# 5_ButtonsAndLeds.net
KiCad netlist of a schematic drawn in Altium Designer
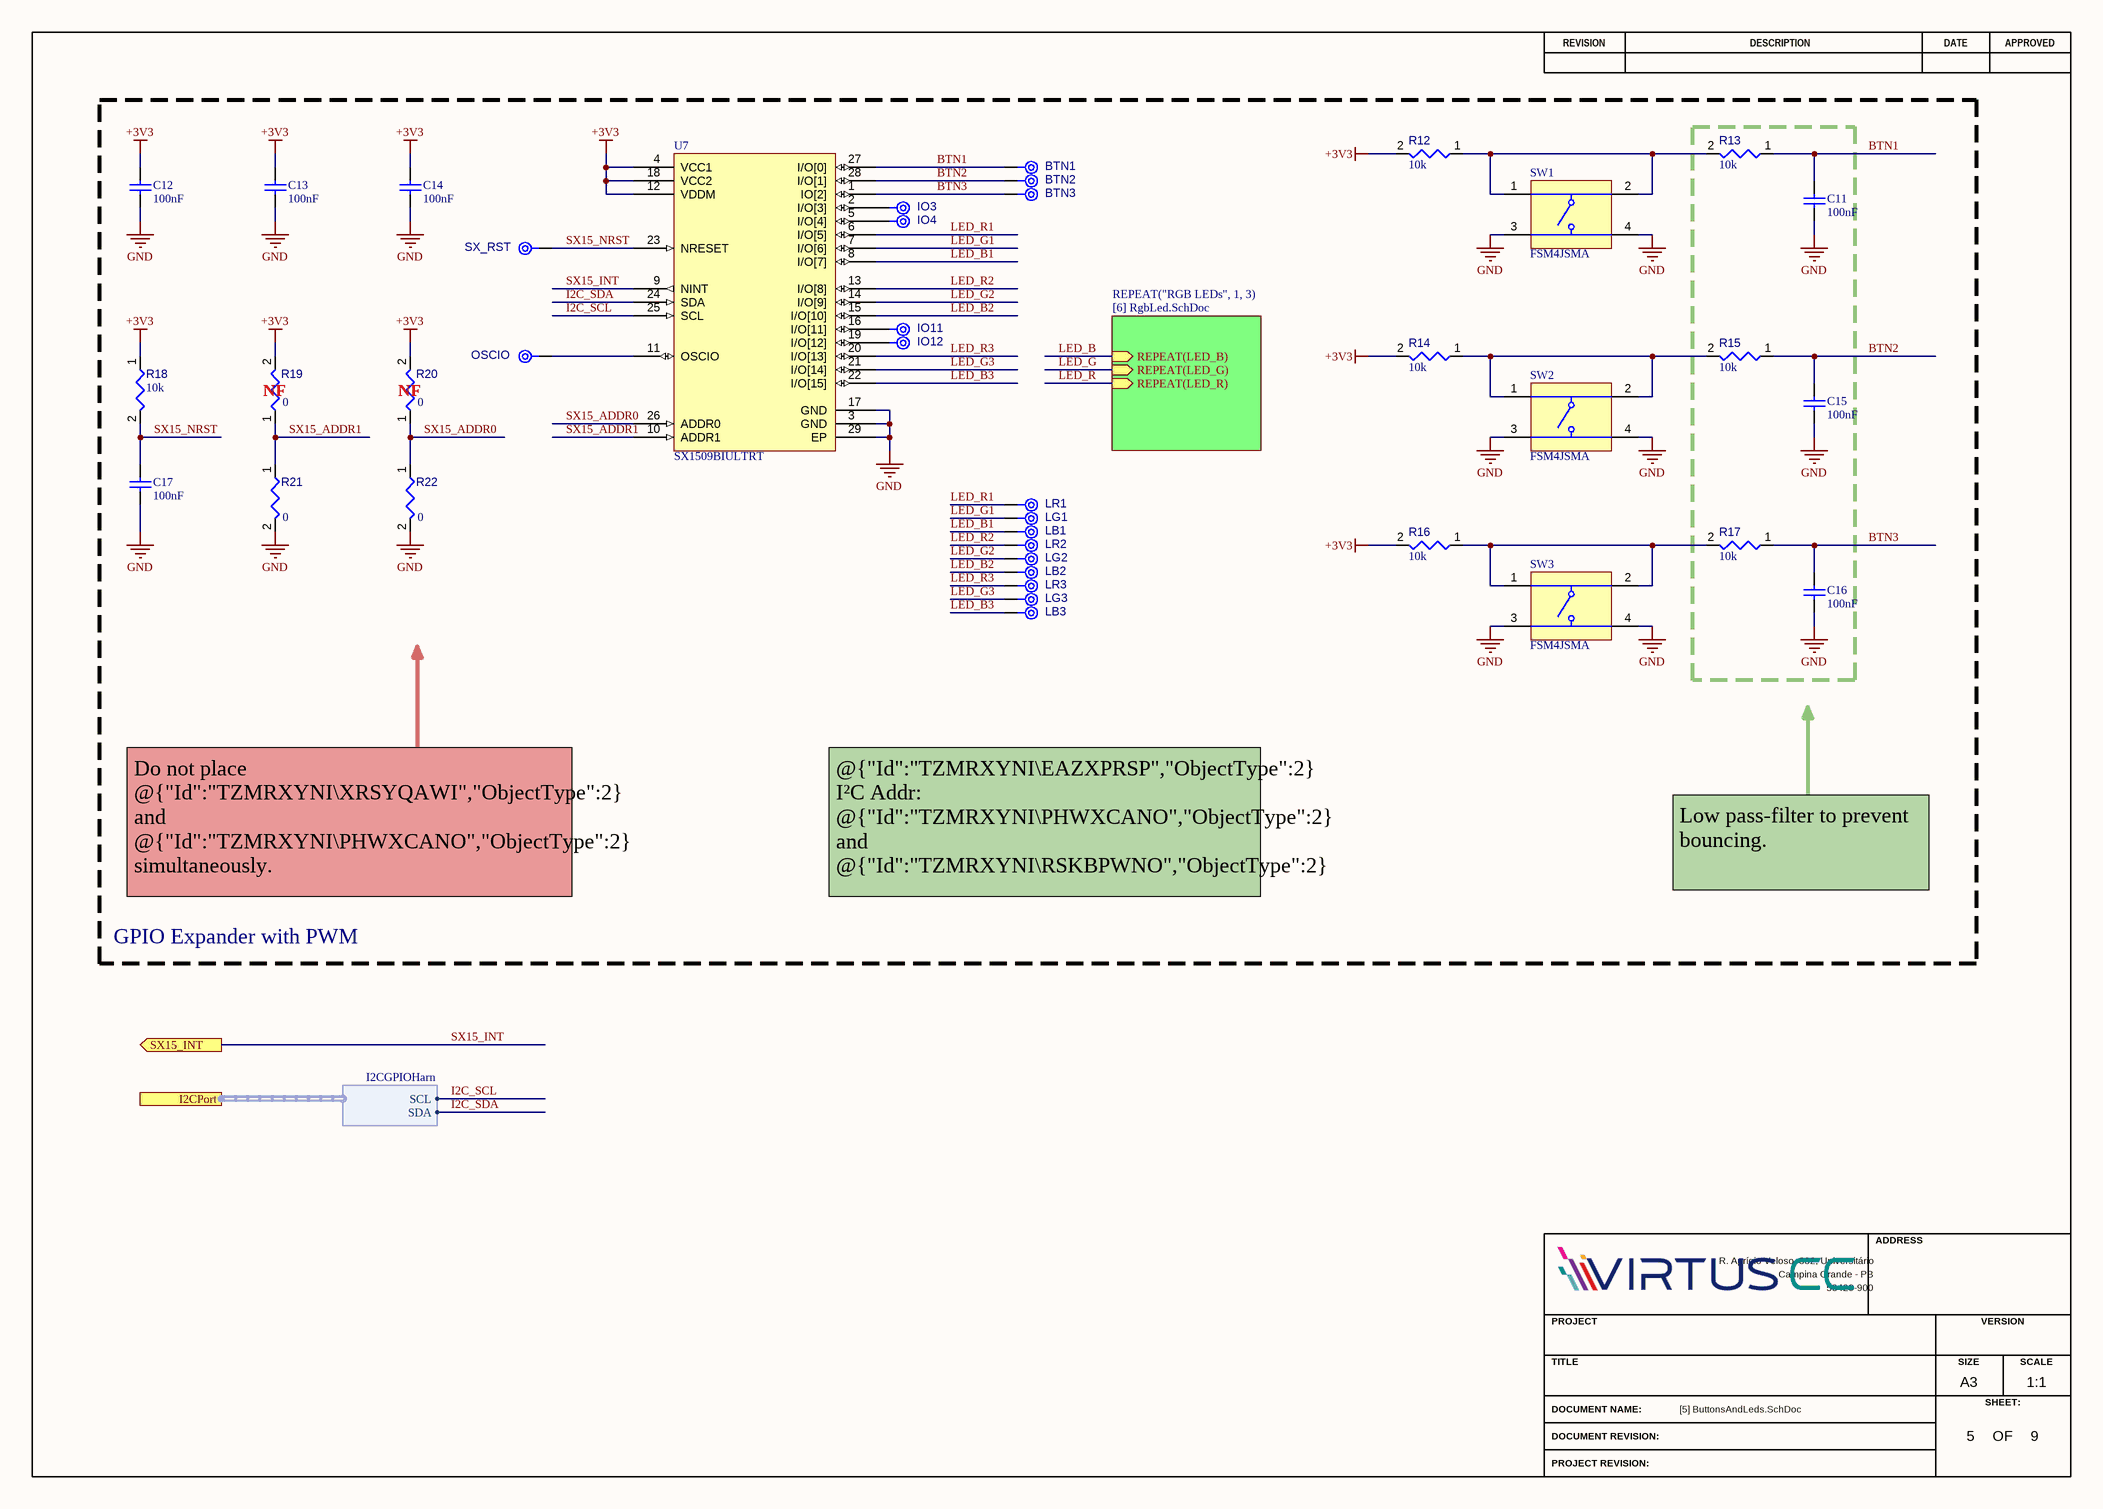
[diagram p0: [5] ButtonsAndLeds.SchDoc]

(export (version "E")
  (design (tool "Eeschema 10.0.6"))
  (components
    (comp (ref "BTN1")
      (value "TPAD6R")
      (footprint "TP06R")
      (description "0.6mm round")
      (libsource (lib "UFCG - Universidade Federal de Campina Grande") (part "CMP-001-0001-4"))
    )
    (comp (ref "BTN2")
      (value "TPAD6R")
      (footprint "TP06R")
      (description "0.6mm round")
      (libsource (lib "UFCG - Universidade Federal de Campina Grande") (part "CMP-001-0001-4"))
    )
    (comp (ref "BTN3")
      (value "TPAD6R")
      (footprint "TP06R")
      (description "0.6mm round")
      (libsource (lib "UFCG - Universidade Federal de Campina Grande") (part "CMP-001-0001-4"))
    )
    (comp (ref "C11")
      (value "100nF")
      (footprint "CAPC0603(1608)100_L")
      (description "Multilayer Ceramic Capacitor, 0.1 uF, 16 V, ± 20%, X7R, 0603 [1608 Metric]")
      (fields (field (name "TOLERANCE") "20%") (field (name "Comment") "VJ0603Y104MXJCW1BC"))
      (libsource (lib "UFCG - Universidade Federal de Campina Grande") (part "CAP"))
    )
    (comp (ref "C12")
      (value "100nF")
      (footprint "CAPC0603(1608)100_L")
      (description "Multilayer Ceramic Capacitor, 0.1 uF, 16 V, ± 20%, X7R, 0603 [1608 Metric]")
      (fields (field (name "TOLERANCE") "20%") (field (name "Comment") "VJ0603Y104MXJCW1BC"))
      (libsource (lib "UFCG - Universidade Federal de Campina Grande") (part "CAP"))
    )
    (comp (ref "C13")
      (value "100nF")
      (footprint "CAPC0603(1608)100_L")
      (description "Multilayer Ceramic Capacitor, 0.1 uF, 16 V, ± 20%, X7R, 0603 [1608 Metric]")
      (fields (field (name "TOLERANCE") "20%") (field (name "Comment") "VJ0603Y104MXJCW1BC"))
      (libsource (lib "UFCG - Universidade Federal de Campina Grande") (part "CAP"))
    )
    (comp (ref "C14")
      (value "100nF")
      (footprint "CAPC0603(1608)100_L")
      (description "Multilayer Ceramic Capacitor, 0.1 uF, 16 V, ± 20%, X7R, 0603 [1608 Metric]")
      (fields (field (name "TOLERANCE") "20%") (field (name "Comment") "VJ0603Y104MXJCW1BC"))
      (libsource (lib "UFCG - Universidade Federal de Campina Grande") (part "CAP"))
    )
    (comp (ref "C15")
      (value "100nF")
      (footprint "CAPC0603(1608)100_L")
      (description "Multilayer Ceramic Capacitor, 0.1 uF, 16 V, ± 20%, X7R, 0603 [1608 Metric]")
      (fields (field (name "TOLERANCE") "20%") (field (name "Comment") "VJ0603Y104MXJCW1BC"))
      (libsource (lib "UFCG - Universidade Federal de Campina Grande") (part "CAP"))
    )
    (comp (ref "C16")
      (value "100nF")
      (footprint "CAPC0603(1608)100_L")
      (description "Multilayer Ceramic Capacitor, 0.1 uF, 16 V, ± 20%, X7R, 0603 [1608 Metric]")
      (fields (field (name "TOLERANCE") "20%") (field (name "Comment") "VJ0603Y104MXJCW1BC"))
      (libsource (lib "UFCG - Universidade Federal de Campina Grande") (part "CAP"))
    )
    (comp (ref "C17")
      (value "100nF")
      (footprint "CAPC0603(1608)100_L")
      (description "Multilayer Ceramic Capacitor, 0.1 uF, 16 V, ± 20%, X7R, 0603 [1608 Metric]")
      (fields (field (name "TOLERANCE") "20%") (field (name "Comment") "VJ0603Y104MXJCW1BC"))
      (libsource (lib "UFCG - Universidade Federal de Campina Grande") (part "CAP"))
    )
    (comp (ref "IO3")
      (value "TPAD6R")
      (footprint "TP06R")
      (description "0.6mm round")
      (libsource (lib "UFCG - Universidade Federal de Campina Grande") (part "CMP-001-0001-4"))
    )
    (comp (ref "IO4")
      (value "TPAD6R")
      (footprint "TP06R")
      (description "0.6mm round")
      (libsource (lib "UFCG - Universidade Federal de Campina Grande") (part "CMP-001-0001-4"))
    )
    (comp (ref "IO11")
      (value "TPAD6R")
      (footprint "TP06R")
      (description "0.6mm round")
      (libsource (lib "UFCG - Universidade Federal de Campina Grande") (part "CMP-001-0001-4"))
    )
    (comp (ref "IO12")
      (value "TPAD6R")
      (footprint "TP06R")
      (description "0.6mm round")
      (libsource (lib "UFCG - Universidade Federal de Campina Grande") (part "CMP-001-0001-4"))
    )
    (comp (ref "LB1")
      (value "TPAD6R")
      (footprint "TP06R")
      (description "0.6mm round")
      (libsource (lib "UFCG - Universidade Federal de Campina Grande") (part "CMP-001-0001-4"))
    )
    (comp (ref "LB2")
      (value "TPAD6R")
      (footprint "TP06R")
      (description "0.6mm round")
      (libsource (lib "UFCG - Universidade Federal de Campina Grande") (part "CMP-001-0001-4"))
    )
    (comp (ref "LB3")
      (value "TPAD6R")
      (footprint "TP06R")
      (description "0.6mm round")
      (libsource (lib "UFCG - Universidade Federal de Campina Grande") (part "CMP-001-0001-4"))
    )
    (comp (ref "LG1")
      (value "TPAD6R")
      (footprint "TP06R")
      (description "0.6mm round")
      (libsource (lib "UFCG - Universidade Federal de Campina Grande") (part "CMP-001-0001-4"))
    )
    (comp (ref "LG2")
      (value "TPAD6R")
      (footprint "TP06R")
      (description "0.6mm round")
      (libsource (lib "UFCG - Universidade Federal de Campina Grande") (part "CMP-001-0001-4"))
    )
    (comp (ref "LG3")
      (value "TPAD6R")
      (footprint "TP06R")
      (description "0.6mm round")
      (libsource (lib "UFCG - Universidade Federal de Campina Grande") (part "CMP-001-0001-4"))
    )
    (comp (ref "LR1")
      (value "TPAD6R")
      (footprint "TP06R")
      (description "0.6mm round")
      (libsource (lib "UFCG - Universidade Federal de Campina Grande") (part "CMP-001-0001-4"))
    )
    (comp (ref "LR2")
      (value "TPAD6R")
      (footprint "TP06R")
      (description "0.6mm round")
      (libsource (lib "UFCG - Universidade Federal de Campina Grande") (part "CMP-001-0001-4"))
    )
    (comp (ref "LR3")
      (value "TPAD6R")
      (footprint "TP06R")
      (description "0.6mm round")
      (libsource (lib "UFCG - Universidade Federal de Campina Grande") (part "CMP-001-0001-4"))
    )
    (comp (ref "OSCIO")
      (value "TPAD6R")
      (footprint "TP06R")
      (description "0.6mm round")
      (libsource (lib "UFCG - Universidade Federal de Campina Grande") (part "CMP-001-0001-4"))
    )
    (comp (ref "R12")
      (value "10k")
      (footprint "RESC0603(1608)_L")
      (description "Chip Resistor, 10 KOhm, +/- 1%, 01 W, -55 to 155 degC, 0603 (1608 Metric)")
      (fields (field (name "POWER") "100mW") (field (name "TOLERANCE") "1%"))
      (libsource (lib "UFCG - Universidade Federal de Campina Grande") (part "RES-2"))
    )
    (comp (ref "R13")
      (value "10k")
      (footprint "RESC0603(1608)_L")
      (description "Chip Resistor, 10 KOhm, +/- 1%, 01 W, -55 to 155 degC, 0603 (1608 Metric)")
      (fields (field (name "POWER") "100mW") (field (name "TOLERANCE") "1%"))
      (libsource (lib "UFCG - Universidade Federal de Campina Grande") (part "RES-2"))
    )
    (comp (ref "R14")
      (value "10k")
      (footprint "RESC0603(1608)_L")
      (description "Chip Resistor, 10 KOhm, +/- 1%, 01 W, -55 to 155 degC, 0603 (1608 Metric)")
      (fields (field (name "POWER") "100mW") (field (name "TOLERANCE") "1%"))
      (libsource (lib "UFCG - Universidade Federal de Campina Grande") (part "RES-2"))
    )
    (comp (ref "R15")
      (value "10k")
      (footprint "RESC0603(1608)_L")
      (description "Chip Resistor, 10 KOhm, +/- 1%, 01 W, -55 to 155 degC, 0603 (1608 Metric)")
      (fields (field (name "POWER") "100mW") (field (name "TOLERANCE") "1%"))
      (libsource (lib "UFCG - Universidade Federal de Campina Grande") (part "RES-2"))
    )
    (comp (ref "R16")
      (value "10k")
      (footprint "RESC0603(1608)_L")
      (description "Chip Resistor, 10 KOhm, +/- 1%, 01 W, -55 to 155 degC, 0603 (1608 Metric)")
      (fields (field (name "POWER") "100mW") (field (name "TOLERANCE") "1%"))
      (libsource (lib "UFCG - Universidade Federal de Campina Grande") (part "RES-2"))
    )
    (comp (ref "R17")
      (value "10k")
      (footprint "RESC0603(1608)_L")
      (description "Chip Resistor, 10 KOhm, +/- 1%, 01 W, -55 to 155 degC, 0603 (1608 Metric)")
      (fields (field (name "POWER") "100mW") (field (name "TOLERANCE") "1%"))
      (libsource (lib "UFCG - Universidade Federal de Campina Grande") (part "RES-2"))
    )
    (comp (ref "R18")
      (value "10k")
      (footprint "RESC0603(1608)_L")
      (description "Chip Resistor, 10 KOhm, +/- 1%, 01 W, -55 to 155 degC, 0603 (1608 Metric)")
      (fields (field (name "POWER") "100mW") (field (name "TOLERANCE") "1%"))
      (libsource (lib "UFCG - Universidade Federal de Campina Grande") (part "RES-2"))
    )
    (comp (ref "R19")
      (value "0")
      (footprint "RESC0603(1608)_L")
      (description "Chip Resistor, 0 Ohm, 0.1 W, -55 to 155 degC, 0603 (1608 Metric)")
      (fields (field (name "TOLERANCE") "5%") (field (name "POWER") "100mW"))
      (libsource (lib "UFCG - Universidade Federal de Campina Grande") (part "RES-2"))
    )
    (comp (ref "R20")
      (value "0")
      (footprint "RESC0603(1608)_L")
      (description "Chip Resistor, 0 Ohm, 0.1 W, -55 to 155 degC, 0603 (1608 Metric)")
      (fields (field (name "TOLERANCE") "5%") (field (name "POWER") "100mW"))
      (libsource (lib "UFCG - Universidade Federal de Campina Grande") (part "RES-2"))
    )
    (comp (ref "R21")
      (value "0")
      (footprint "RESC0603(1608)_L")
      (description "Chip Resistor, 0 Ohm, 0.1 W, -55 to 155 degC, 0603 (1608 Metric)")
      (fields (field (name "TOLERANCE") "5%") (field (name "POWER") "100mW"))
      (libsource (lib "UFCG - Universidade Federal de Campina Grande") (part "RES-2"))
    )
    (comp (ref "R22")
      (value "0")
      (footprint "RESC0603(1608)_L")
      (description "Chip Resistor, 0 Ohm, 0.1 W, -55 to 155 degC, 0603 (1608 Metric)")
      (fields (field (name "TOLERANCE") "5%") (field (name "POWER") "100mW"))
      (libsource (lib "UFCG - Universidade Federal de Campina Grande") (part "RES-2"))
    )
    (comp (ref "SW1")
      (value "FSM4JSMA")
      (footprint "TECO-FSM4JSMA_V")
      (description "Switch Tactile OFF (ON) SPST Round Button Gull Wing 0.05A 12VDC 1.57N SMD Loose Piece")
      (libsource (lib "UFCG - Universidade Federal de Campina Grande") (part "SW-SPST-4_A"))
    )
    (comp (ref "SW2")
      (value "FSM4JSMA")
      (footprint "TECO-FSM4JSMA_V")
      (description "Switch Tactile OFF (ON) SPST Round Button Gull Wing 0.05A 12VDC 1.57N SMD Loose Piece")
      (libsource (lib "UFCG - Universidade Federal de Campina Grande") (part "SW-SPST-4_A"))
    )
    (comp (ref "SW3")
      (value "FSM4JSMA")
      (footprint "TECO-FSM4JSMA_V")
      (description "Switch Tactile OFF (ON) SPST Round Button Gull Wing 0.05A 12VDC 1.57N SMD Loose Piece")
      (libsource (lib "UFCG - Universidade Federal de Campina Grande") (part "SW-SPST-4_A"))
    )
    (comp (ref "SX_RST")
      (value "TPAD6R")
      (footprint "TP06R")
      (description "0.6mm round")
      (libsource (lib "UFCG - Universidade Federal de Campina Grande") (part "CMP-001-0001-4"))
    )
    (comp (ref "U7")
      (value "SX1509BIULTRT")
      (footprint "QFN40P410X410X60_HS-29N")
      (description "IC Gpio Expander I2C 16CH 28QFN / I2C Interface 5.5V 28-PIN Qfn-ut Ep T/r")
      (libsource (lib "UFCG - Universidade Federal de Campina Grande") (part "New symbol 1"))
    )
  )
  (nets
    (net (code "2") (name "+3V3") (class "Default")
      (node (ref "C12") (pin "2") (pinfunction "2_2") (pintype "passive"))
      (node (ref "C13") (pin "2") (pinfunction "2_2") (pintype "passive"))
      (node (ref "C14") (pin "2") (pinfunction "2_2") (pintype "passive"))
      (node (ref "R12") (pin "2") (pinfunction "2_2") (pintype "passive"))
      (node (ref "R14") (pin "2") (pinfunction "2_2") (pintype "passive"))
      (node (ref "R16") (pin "2") (pinfunction "2_2") (pintype "passive"))
      (node (ref "R18") (pin "1") (pinfunction "1_1") (pintype "passive"))
      (node (ref "R19") (pin "2") (pinfunction "2_2") (pintype "passive"))
      (node (ref "R20") (pin "2") (pinfunction "2_2") (pintype "passive"))
      (node (ref "U7") (pin "12") (pinfunction "VDDM_12") (pintype "power_in"))
      (node (ref "U7") (pin "18") (pinfunction "VCC2_18") (pintype "power_in"))
      (node (ref "U7") (pin "4") (pinfunction "VCC1_4") (pintype "power_in"))
    )
    (net (code "3") (name "/BTN1") (class "Default")
      (node (ref "BTN1") (pin "1") (pinfunction "TP_1") (pintype "passive"))
      (node (ref "C11") (pin "2") (pinfunction "2_2") (pintype "passive"))
      (node (ref "R13") (pin "1") (pinfunction "1_1") (pintype "passive"))
      (node (ref "U7") (pin "27") (pinfunction "I/O[0]_27") (pintype "bidirectional"))
    )
    (net (code "4") (name "/BTN2") (class "Default")
      (node (ref "BTN2") (pin "1") (pinfunction "TP_1") (pintype "passive"))
      (node (ref "C15") (pin "2") (pinfunction "2_2") (pintype "passive"))
      (node (ref "R15") (pin "1") (pinfunction "1_1") (pintype "passive"))
      (node (ref "U7") (pin "28") (pinfunction "I/O[1]_28") (pintype "bidirectional"))
    )
    (net (code "5") (name "/BTN3") (class "Default")
      (node (ref "BTN3") (pin "1") (pinfunction "TP_1") (pintype "passive"))
      (node (ref "C16") (pin "2") (pinfunction "2_2") (pintype "passive"))
      (node (ref "R17") (pin "1") (pinfunction "1_1") (pintype "passive"))
      (node (ref "U7") (pin "1") (pinfunction "IO[2]_1") (pintype "bidirectional"))
    )
    (net (code "6") (name "/I2C_SCL") (class "Default")
      (node (ref "U7") (pin "25") (pinfunction "SCL_25") (pintype "input"))
    )
    (net (code "7") (name "/I2C_SDA") (class "Default")
      (node (ref "U7") (pin "24") (pinfunction "SDA_24") (pintype "input"))
    )
    (net (code "9") (name "/LED_B1") (class "Default")
      (node (ref "LB1") (pin "1") (pinfunction "TP_1") (pintype "passive"))
      (node (ref "U7") (pin "8") (pinfunction "I/O[7]_8") (pintype "bidirectional"))
    )
    (net (code "10") (name "/LED_B2") (class "Default")
      (node (ref "LB2") (pin "1") (pinfunction "TP_1") (pintype "passive"))
      (node (ref "U7") (pin "15") (pinfunction "I/O[10]_15") (pintype "bidirectional"))
    )
    (net (code "11") (name "/LED_B3") (class "Default")
      (node (ref "LB3") (pin "1") (pinfunction "TP_1") (pintype "passive"))
      (node (ref "U7") (pin "22") (pinfunction "I/O[15]_22") (pintype "bidirectional"))
    )
    (net (code "13") (name "/LED_G1") (class "Default")
      (node (ref "LG1") (pin "1") (pinfunction "TP_1") (pintype "passive"))
      (node (ref "U7") (pin "7") (pinfunction "I/O[6]_7") (pintype "bidirectional"))
    )
    (net (code "14") (name "/LED_G2") (class "Default")
      (node (ref "LG2") (pin "1") (pinfunction "TP_1") (pintype "passive"))
      (node (ref "U7") (pin "14") (pinfunction "I/O[9]_14") (pintype "bidirectional"))
    )
    (net (code "15") (name "/LED_G3") (class "Default")
      (node (ref "LG3") (pin "1") (pinfunction "TP_1") (pintype "passive"))
      (node (ref "U7") (pin "21") (pinfunction "I/O[14]_21") (pintype "bidirectional"))
    )
    (net (code "17") (name "/LED_R1") (class "Default")
      (node (ref "LR1") (pin "1") (pinfunction "TP_1") (pintype "passive"))
      (node (ref "U7") (pin "6") (pinfunction "I/O[5]_6") (pintype "bidirectional"))
    )
    (net (code "18") (name "/LED_R2") (class "Default")
      (node (ref "LR2") (pin "1") (pinfunction "TP_1") (pintype "passive"))
      (node (ref "U7") (pin "13") (pinfunction "I/O[8]_13") (pintype "bidirectional"))
    )
    (net (code "19") (name "/LED_R3") (class "Default")
      (node (ref "LR3") (pin "1") (pinfunction "TP_1") (pintype "passive"))
      (node (ref "U7") (pin "20") (pinfunction "I/O[13]_20") (pintype "bidirectional"))
    )
    (net (code "20") (name "/SX15_ADDR0") (class "Default")
      (node (ref "R20") (pin "1") (pinfunction "1_1") (pintype "passive"))
      (node (ref "R22") (pin "1") (pinfunction "1_1") (pintype "passive"))
      (node (ref "U7") (pin "26") (pinfunction "ADDR0_26") (pintype "input"))
    )
    (net (code "21") (name "/SX15_ADDR1") (class "Default")
      (node (ref "R19") (pin "1") (pinfunction "1_1") (pintype "passive"))
      (node (ref "R21") (pin "1") (pinfunction "1_1") (pintype "passive"))
      (node (ref "U7") (pin "10") (pinfunction "ADDR1_10") (pintype "input"))
    )
    (net (code "22") (name "/SX15_INT") (class "Default")
      (node (ref "U7") (pin "9") (pinfunction "NINT_9") (pintype "output"))
    )
    (net (code "23") (name "/SX15_NRST") (class "Default")
      (node (ref "C17") (pin "2") (pinfunction "2_2") (pintype "passive"))
      (node (ref "R18") (pin "2") (pinfunction "2_2") (pintype "passive"))
      (node (ref "SX_RST") (pin "1") (pinfunction "TP_1") (pintype "passive"))
      (node (ref "U7") (pin "23") (pinfunction "NRESET_23") (pintype "input"))
    )
    (net (code "25") (name "GND") (class "Default")
      (node (ref "C11") (pin "1") (pinfunction "1_1") (pintype "passive"))
      (node (ref "C12") (pin "1") (pinfunction "1_1") (pintype "passive"))
      (node (ref "C13") (pin "1") (pinfunction "1_1") (pintype "passive"))
      (node (ref "C14") (pin "1") (pinfunction "1_1") (pintype "passive"))
      (node (ref "C15") (pin "1") (pinfunction "1_1") (pintype "passive"))
      (node (ref "C16") (pin "1") (pinfunction "1_1") (pintype "passive"))
      (node (ref "C17") (pin "1") (pinfunction "1_1") (pintype "passive"))
      (node (ref "R21") (pin "2") (pinfunction "2_2") (pintype "passive"))
      (node (ref "R22") (pin "2") (pinfunction "2_2") (pintype "passive"))
      (node (ref "SW1") (pin "3") (pinfunction "3_3") (pintype "passive"))
      (node (ref "SW1") (pin "4") (pinfunction "4_4") (pintype "passive"))
      (node (ref "SW2") (pin "3") (pinfunction "3_3") (pintype "passive"))
      (node (ref "SW2") (pin "4") (pinfunction "4_4") (pintype "passive"))
      (node (ref "SW3") (pin "3") (pinfunction "3_3") (pintype "passive"))
      (node (ref "SW3") (pin "4") (pinfunction "4_4") (pintype "passive"))
      (node (ref "U7") (pin "17") (pinfunction "GND_17") (pintype "power_in"))
      (node (ref "U7") (pin "29") (pinfunction "EP_29") (pintype "power_in"))
      (node (ref "U7") (pin "3") (pinfunction "GND_3") (pintype "power_in"))
    )
    (net (code "26") (name "Net-(IO3-TP)") (class "Default")
      (node (ref "IO3") (pin "1") (pinfunction "TP_1") (pintype "passive"))
      (node (ref "U7") (pin "2") (pinfunction "I/O[3]_2") (pintype "bidirectional"))
    )
    (net (code "27") (name "Net-(IO4-TP)") (class "Default")
      (node (ref "IO4") (pin "1") (pinfunction "TP_1") (pintype "passive"))
      (node (ref "U7") (pin "5") (pinfunction "I/O[4]_5") (pintype "bidirectional"))
    )
    (net (code "28") (name "Net-(IO11-TP)") (class "Default")
      (node (ref "IO11") (pin "1") (pinfunction "TP_1") (pintype "passive"))
      (node (ref "U7") (pin "16") (pinfunction "I/O[11]_16") (pintype "bidirectional"))
    )
    (net (code "29") (name "Net-(IO12-TP)") (class "Default")
      (node (ref "IO12") (pin "1") (pinfunction "TP_1") (pintype "passive"))
      (node (ref "U7") (pin "19") (pinfunction "I/O[12]_19") (pintype "bidirectional"))
    )
    (net (code "30") (name "Net-(OSCIO-TP)") (class "Default")
      (node (ref "OSCIO") (pin "1") (pinfunction "TP_1") (pintype "passive"))
      (node (ref "U7") (pin "11") (pinfunction "OSCIO_11") (pintype "bidirectional"))
    )
    (net (code "31") (name "Net-(R12-Pad1)") (class "Default")
      (node (ref "R12") (pin "1") (pinfunction "1_1") (pintype "passive"))
      (node (ref "R13") (pin "2") (pinfunction "2_2") (pintype "passive"))
      (node (ref "SW1") (pin "1") (pinfunction "1_1") (pintype "passive"))
      (node (ref "SW1") (pin "2") (pinfunction "2_2") (pintype "passive"))
    )
    (net (code "32") (name "Net-(R14-Pad1)") (class "Default")
      (node (ref "R14") (pin "1") (pinfunction "1_1") (pintype "passive"))
      (node (ref "R15") (pin "2") (pinfunction "2_2") (pintype "passive"))
      (node (ref "SW2") (pin "1") (pinfunction "1_1") (pintype "passive"))
      (node (ref "SW2") (pin "2") (pinfunction "2_2") (pintype "passive"))
    )
    (net (code "33") (name "Net-(R16-Pad1)") (class "Default")
      (node (ref "R16") (pin "1") (pinfunction "1_1") (pintype "passive"))
      (node (ref "R17") (pin "2") (pinfunction "2_2") (pintype "passive"))
      (node (ref "SW3") (pin "1") (pinfunction "1_1") (pintype "passive"))
      (node (ref "SW3") (pin "2") (pinfunction "2_2") (pintype "passive"))
    )
  )
)
